# tps63020-buck-boost-flashlight-driver-17.net
KiCad netlist of a schematic drawn in EAGLE
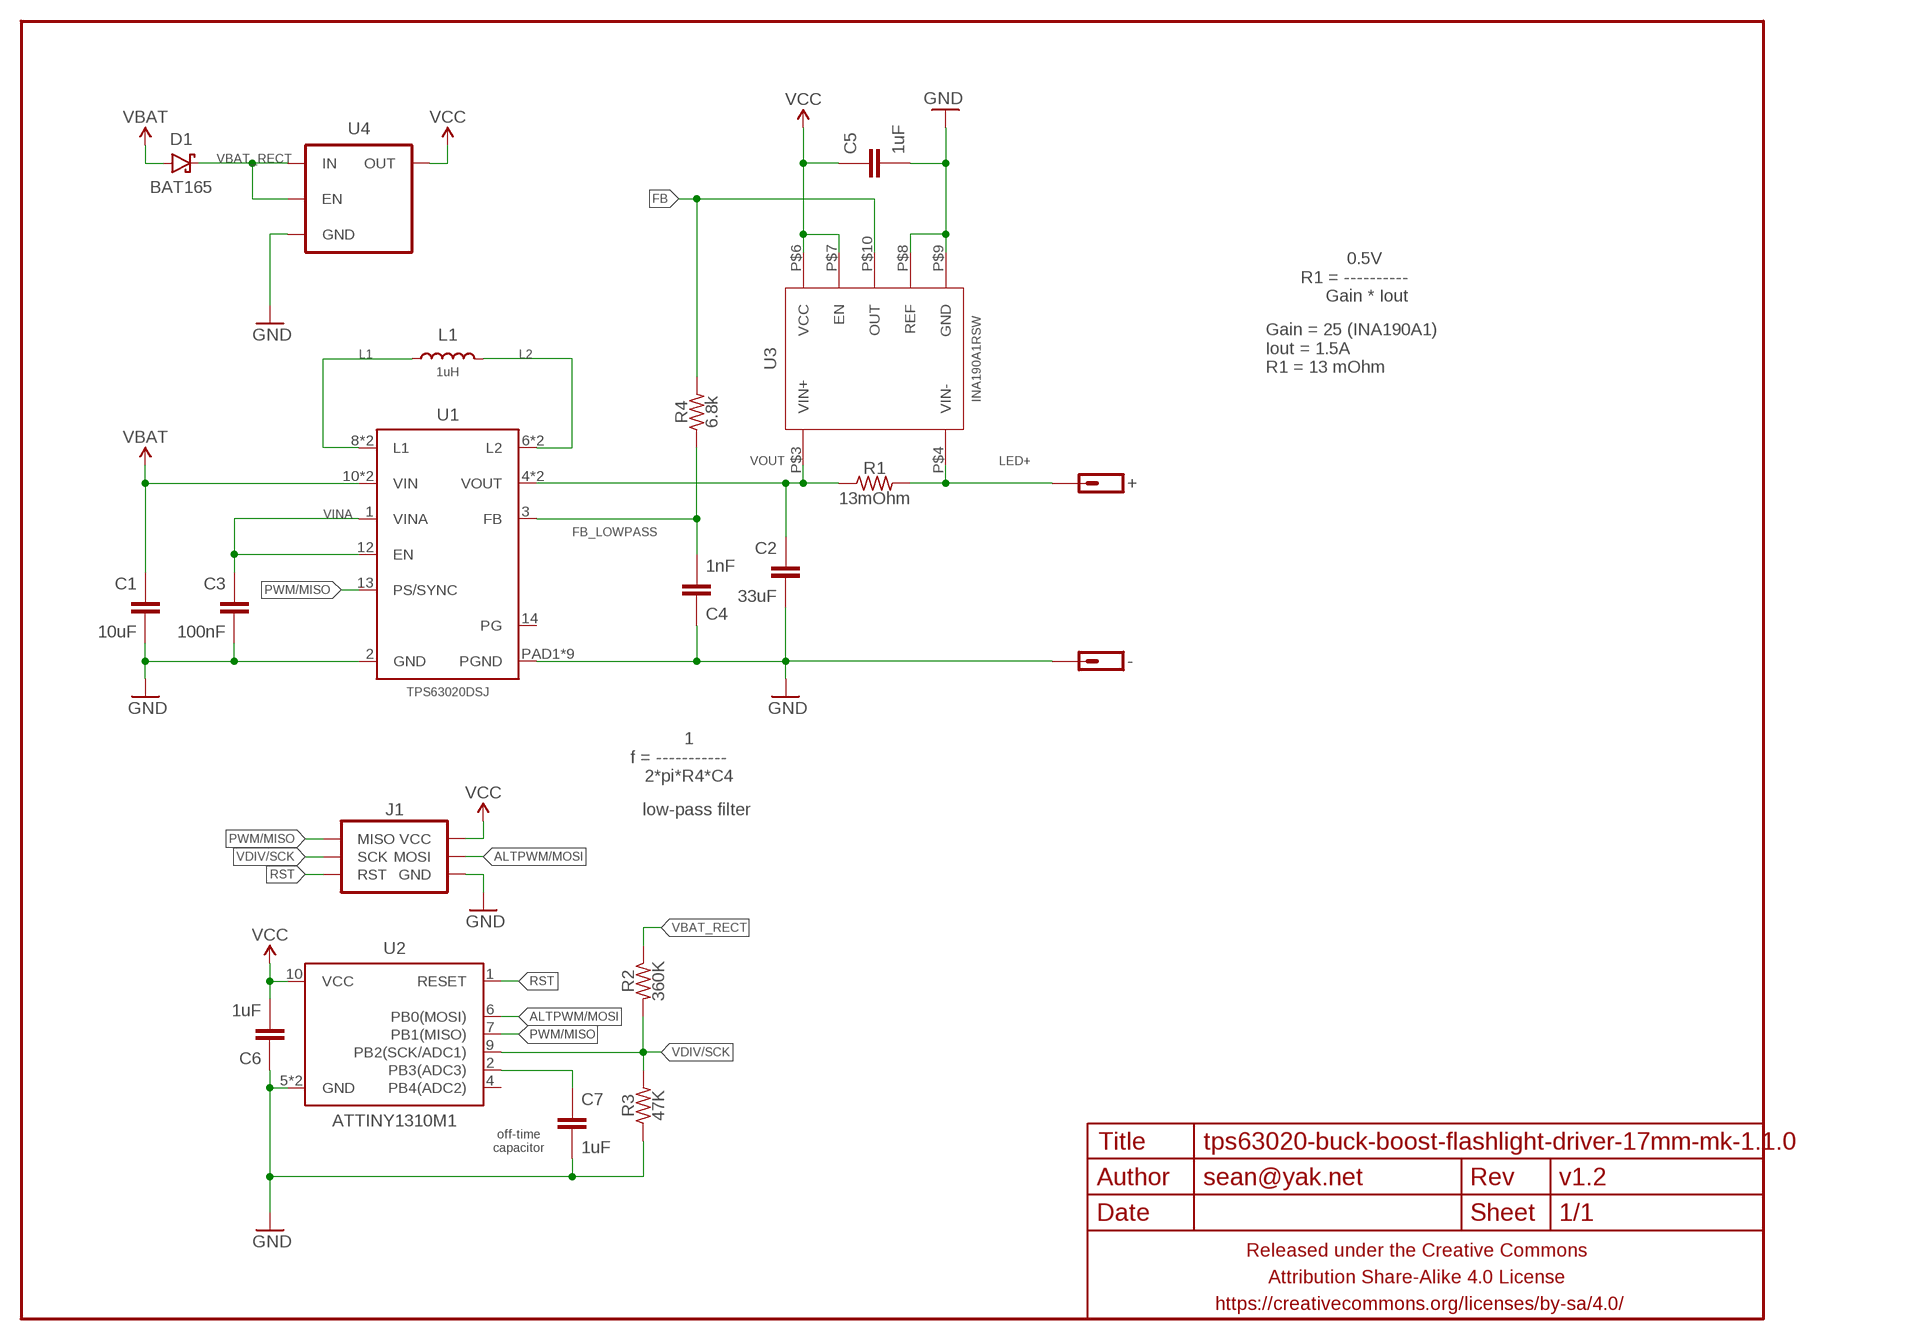
[diagram p0: schematic, sheet 1]

(export (version "E")
  (design (tool "Eeschema 10.0.6"))
  (components
    (comp (ref "+")
      (value "M01SMD-1.6MMX3.2MM")
      (footprint "eagle-import:1X01-SMD-1.6MMX3.2MM")
      (libsource (lib "eagle-import") (part "M01SMD-1.6MMX3.2MM"))
    )
    (comp (ref "-")
      (value "M01SMD-1.6MMX3.2MM")
      (footprint "eagle-import:1X01-SMD-1.6MMX3.2MM")
      (libsource (lib "eagle-import") (part "M01SMD-1.6MMX3.2MM"))
    )
    (comp (ref "C1")
      (value "10uF")
      (footprint "eagle-import:C0805-TIGHTER")
      (libsource (lib "eagle-import") (part "CAPACITOR-CERAMICC0805-TIGHTER"))
    )
    (comp (ref "C2")
      (value "33uF")
      (footprint "eagle-import:C1206")
      (libsource (lib "eagle-import") (part "CAPACITOR-CERAMICC1206"))
    )
    (comp (ref "C3")
      (value "100nF")
      (footprint "eagle-import:C0402")
      (libsource (lib "eagle-import") (part "CAPACITOR-CERAMICC0402"))
    )
    (comp (ref "C4")
      (value "1nF")
      (footprint "eagle-import:C0402")
      (libsource (lib "eagle-import") (part "CAPACITOR-CERAMICC0402"))
    )
    (comp (ref "C5")
      (value "1uF")
      (footprint "eagle-import:C0402")
      (libsource (lib "eagle-import") (part "CAPACITOR-CERAMICC0402"))
    )
    (comp (ref "C6")
      (value "1uF")
      (footprint "eagle-import:C0402")
      (libsource (lib "eagle-import") (part "CAPACITOR-CERAMICC0402"))
    )
    (comp (ref "C7")
      (value "1uF")
      (footprint "eagle-import:C0402")
      (libsource (lib "eagle-import") (part "CAPACITOR-CERAMICC0402"))
    )
    (comp (ref "D1")
      (value "BAT165")
      (footprint "eagle-import:SOD323-SCHOTTKY")
      (libsource (lib "eagle-import") (part "DIODE-SCHOTTKYSOD323"))
    )
    (comp (ref "FRAME1")
      (value "FRAME-LETTERNO_PACKAGE")
      (footprint "eagle-import:DUMMY")
      (fields
        (field (name "DESIGNER") "sean@yak.net")
        (field (name "VERSION") "v1.2")
        (field (name "DESIGNER_1") "sean@yak.net")
        (field (name "VERSION_1") "v1.2")
      )
      (libsource (lib "eagle-import") (part "FRAME-LETTERNO_PACKAGE"))
    )
    (comp (ref "J1")
      (value "AVR_SPI_PRG_6SMD-1.27MM")
      (footprint "eagle-import:2X3-1.27MM-SMD")
      (libsource (lib "eagle-import") (part "AVR_SPI_PRG_6SMD-1.27MM"))
    )
    (comp (ref "L1")
      (value "1uH")
      (footprint "eagle-import:XAL50X0")
      (libsource (lib "eagle-import") (part "INDUCTORXAL50X0"))
    )
    (comp (ref "R1")
      (value "13mOhm")
      (footprint "eagle-import:R1206")
      (libsource (lib "eagle-import") (part "RESISTORR1206"))
    )
    (comp (ref "R2")
      (value "360K")
      (footprint "eagle-import:R0402")
      (libsource (lib "eagle-import") (part "RESISTORR0402"))
    )
    (comp (ref "R3")
      (value "47K")
      (footprint "eagle-import:R0402")
      (libsource (lib "eagle-import") (part "RESISTORR0402"))
    )
    (comp (ref "R4")
      (value "6.8k")
      (footprint "eagle-import:R0402")
      (libsource (lib "eagle-import") (part "RESISTORR0402"))
    )
    (comp (ref "U1")
      (value "TPS63020DSJ")
      (footprint "eagle-import:VSON-14-4MMX3MM")
      (libsource (lib "eagle-import") (part "TPS63020DSJ"))
    )
    (comp (ref "U2")
      (value "ATTINY1310M1")
      (footprint "eagle-import:QFN10(2X5)")
      (libsource (lib "eagle-import") (part "ATTINY1310M1"))
    )
    (comp (ref "U3")
      (value "INA190A1RSW")
      (footprint "eagle-import:UQFN-10")
      (libsource (lib "eagle-import") (part "INA190RSW"))
    )
    (comp (ref "U4")
      (value "V_REG_ENTLV700")
      (footprint "eagle-import:SC70")
      (libsource (lib "eagle-import") (part "V_REG_ENTLV700"))
    )
  )
  (nets
    (net (code "1") (name "/FB_LOWPASS") (class "Default")
      (node (ref "C4") (pin "2") (pinfunction "2_2") (pintype "passive"))
      (node (ref "R4") (pin "1") (pinfunction "1_1") (pintype "passive"))
      (node (ref "U1") (pin "3") (pinfunction "FB_3") (pintype "bidirectional"))
    )
    (net (code "2") (name "/L1") (class "Default")
      (node (ref "L1") (pin "P$1") (pinfunction "1_P$1") (pintype "passive"))
      (node (ref "U1") (pin "8") (pinfunction "L1_8") (pintype "bidirectional"))
      (node (ref "U1") (pin "9") (pinfunction "L1_9") (pintype "bidirectional"))
    )
    (net (code "3") (name "/L2") (class "Default")
      (node (ref "L1") (pin "P$2") (pinfunction "2_P$2") (pintype "passive"))
      (node (ref "U1") (pin "6") (pinfunction "L2_6") (pintype "bidirectional"))
      (node (ref "U1") (pin "7") (pinfunction "L2_7") (pintype "bidirectional"))
    )
    (net (code "4") (name "/LED+") (class "Default")
      (node (ref "+") (pin "P$1") (pinfunction "1_P$1") (pintype "passive"))
      (node (ref "R1") (pin "2") (pinfunction "2_2") (pintype "passive"))
      (node (ref "U3") (pin "P$4") (pinfunction "VIN-_P$4") (pintype "bidirectional"))
    )
    (net (code "5") (name "/VINA") (class "Default")
      (node (ref "C3") (pin "1") (pinfunction "1_1") (pintype "passive"))
      (node (ref "U1") (pin "1") (pinfunction "VINA_1") (pintype "bidirectional"))
      (node (ref "U1") (pin "12") (pinfunction "EN_12") (pintype "bidirectional"))
    )
    (net (code "6") (name "/VOUT") (class "Default")
      (node (ref "C2") (pin "1") (pinfunction "1_1") (pintype "passive"))
      (node (ref "R1") (pin "1") (pinfunction "1_1") (pintype "passive"))
      (node (ref "U1") (pin "4") (pinfunction "VOUT_4") (pintype "bidirectional"))
      (node (ref "U1") (pin "5") (pinfunction "VOUT_5") (pintype "bidirectional"))
      (node (ref "U3") (pin "P$3") (pinfunction "VIN+_P$3") (pintype "bidirectional"))
    )
    (net (code "7") (name "ALTPWM{slash}MOSI") (class "Default")
      (node (ref "J1") (pin "4") (pinfunction "MOSI_4") (pintype "passive"))
      (node (ref "U2") (pin "6") (pinfunction "PB0(MOSI)_6") (pintype "bidirectional"))
    )
    (net (code "8") (name "FB") (class "Default")
      (node (ref "R4") (pin "2") (pinfunction "2_2") (pintype "passive"))
      (node (ref "U3") (pin "P$10") (pinfunction "OUT_P$10") (pintype "bidirectional"))
    )
    (net (code "9") (name "GND") (class "Default")
      (node (ref "-") (pin "P$1") (pinfunction "1_P$1") (pintype "passive"))
      (node (ref "C1") (pin "2") (pinfunction "2_2") (pintype "passive"))
      (node (ref "C2") (pin "2") (pinfunction "2_2") (pintype "passive"))
      (node (ref "C3") (pin "2") (pinfunction "2_2") (pintype "passive"))
      (node (ref "C4") (pin "1") (pinfunction "1_1") (pintype "passive"))
      (node (ref "C5") (pin "2") (pinfunction "2_2") (pintype "passive"))
      (node (ref "C6") (pin "1") (pinfunction "1_1") (pintype "passive"))
      (node (ref "C7") (pin "2") (pinfunction "2_2") (pintype "passive"))
      (node (ref "J1") (pin "6") (pinfunction "GND_6") (pintype "passive"))
      (node (ref "R3") (pin "1") (pinfunction "1_1") (pintype "passive"))
      (node (ref "U1") (pin "2") (pinfunction "GND_2") (pintype "bidirectional"))
      (node (ref "U1") (pin "PAD1") (pinfunction "PGND_PAD1") (pintype "bidirectional"))
      (node (ref "U1") (pin "PAD2") (pinfunction "PGND_PAD2") (pintype "bidirectional"))
      (node (ref "U1") (pin "PAD3") (pinfunction "PGND_PAD3") (pintype "bidirectional"))
      (node (ref "U1") (pin "PAD4") (pinfunction "PGND_PAD4") (pintype "bidirectional"))
      (node (ref "U1") (pin "PAD5") (pinfunction "PGND_PAD5") (pintype "bidirectional"))
      (node (ref "U1") (pin "PAD6") (pinfunction "PGND_PAD6") (pintype "bidirectional"))
      (node (ref "U1") (pin "PAD7") (pinfunction "PGND_PAD7") (pintype "bidirectional"))
      (node (ref "U1") (pin "PAD8") (pinfunction "PGND_PAD8") (pintype "bidirectional"))
      (node (ref "U1") (pin "PADCENTER") (pinfunction "PGND_PADCENTER") (pintype "bidirectional"))
      (node (ref "U2") (pin "5") (pinfunction "GND_5") (pintype "bidirectional"))
      (node (ref "U2") (pin "PAD") (pinfunction "GND_PAD") (pintype "bidirectional"))
      (node (ref "U3") (pin "P$8") (pinfunction "REF_P$8") (pintype "bidirectional"))
      (node (ref "U3") (pin "P$9") (pinfunction "GND_P$9") (pintype "bidirectional"))
      (node (ref "U4") (pin "2") (pinfunction "GND_2") (pintype "input"))
    )
    (net (code "10") (name "Net-(U2-PB3(ADC3))") (class "Default")
      (node (ref "C7") (pin "1") (pinfunction "1_1") (pintype "passive"))
      (node (ref "U2") (pin "2") (pinfunction "PB3(ADC3)_2") (pintype "bidirectional"))
    )
    (net (code "11") (name "PWM{slash}MISO") (class "Default")
      (node (ref "J1") (pin "1") (pinfunction "MISO_1") (pintype "passive"))
      (node (ref "U1") (pin "13") (pinfunction "PS/SYNC_13") (pintype "bidirectional"))
      (node (ref "U2") (pin "7") (pinfunction "PB1(MISO)_7") (pintype "bidirectional"))
    )
    (net (code "12") (name "RST") (class "Default")
      (node (ref "J1") (pin "5") (pinfunction "RST_5") (pintype "passive"))
      (node (ref "U2") (pin "1") (pinfunction "RESET_1") (pintype "bidirectional"))
    )
    (net (code "13") (name "VBAT") (class "Default")
      (node (ref "C1") (pin "1") (pinfunction "1_1") (pintype "passive"))
      (node (ref "D1") (pin "A") (pinfunction "A_A") (pintype "passive"))
      (node (ref "U1") (pin "10") (pinfunction "VIN_10") (pintype "bidirectional"))
      (node (ref "U1") (pin "11") (pinfunction "VIN_11") (pintype "bidirectional"))
    )
    (net (code "14") (name "VBAT_RECT") (class "Default")
      (node (ref "D1") (pin "C") (pinfunction "C_C") (pintype "passive"))
      (node (ref "R2") (pin "1") (pinfunction "1_1") (pintype "passive"))
      (node (ref "U4") (pin "1") (pinfunction "IN_1") (pintype "input"))
      (node (ref "U4") (pin "3") (pinfunction "EN_3") (pintype "input"))
    )
    (net (code "15") (name "VCC") (class "Default")
      (node (ref "C5") (pin "1") (pinfunction "1_1") (pintype "passive"))
      (node (ref "C6") (pin "2") (pinfunction "2_2") (pintype "passive"))
      (node (ref "J1") (pin "2") (pinfunction "VCC_2") (pintype "passive"))
      (node (ref "U2") (pin "10") (pinfunction "VCC_10") (pintype "bidirectional"))
      (node (ref "U3") (pin "P$6") (pinfunction "VCC_P$6") (pintype "bidirectional"))
      (node (ref "U3") (pin "P$7") (pinfunction "EN_P$7") (pintype "bidirectional"))
      (node (ref "U4") (pin "5") (pinfunction "OUT_5") (pintype "passive"))
    )
    (net (code "16") (name "VDIV{slash}SCK") (class "Default")
      (node (ref "J1") (pin "3") (pinfunction "SCK_3") (pintype "passive"))
      (node (ref "R2") (pin "2") (pinfunction "2_2") (pintype "passive"))
      (node (ref "R3") (pin "2") (pinfunction "2_2") (pintype "passive"))
      (node (ref "U2") (pin "9") (pinfunction "PB2(SCK/ADC1)_9") (pintype "bidirectional"))
    )
    (net (code "17") (name "unconnected-(U1-PG-Pad14)") (class "Default")
      (node (ref "U1") (pin "14") (pinfunction "PG_14") (pintype "bidirectional"))
    )
    (net (code "18") (name "unconnected-(U2-PB4(ADC2)-Pad4)") (class "Default")
      (node (ref "U2") (pin "4") (pinfunction "PB4(ADC2)_4") (pintype "bidirectional"))
    )
  )
)
